# Connect.net
KiCad netlist of a schematic drawn in Altium Designer
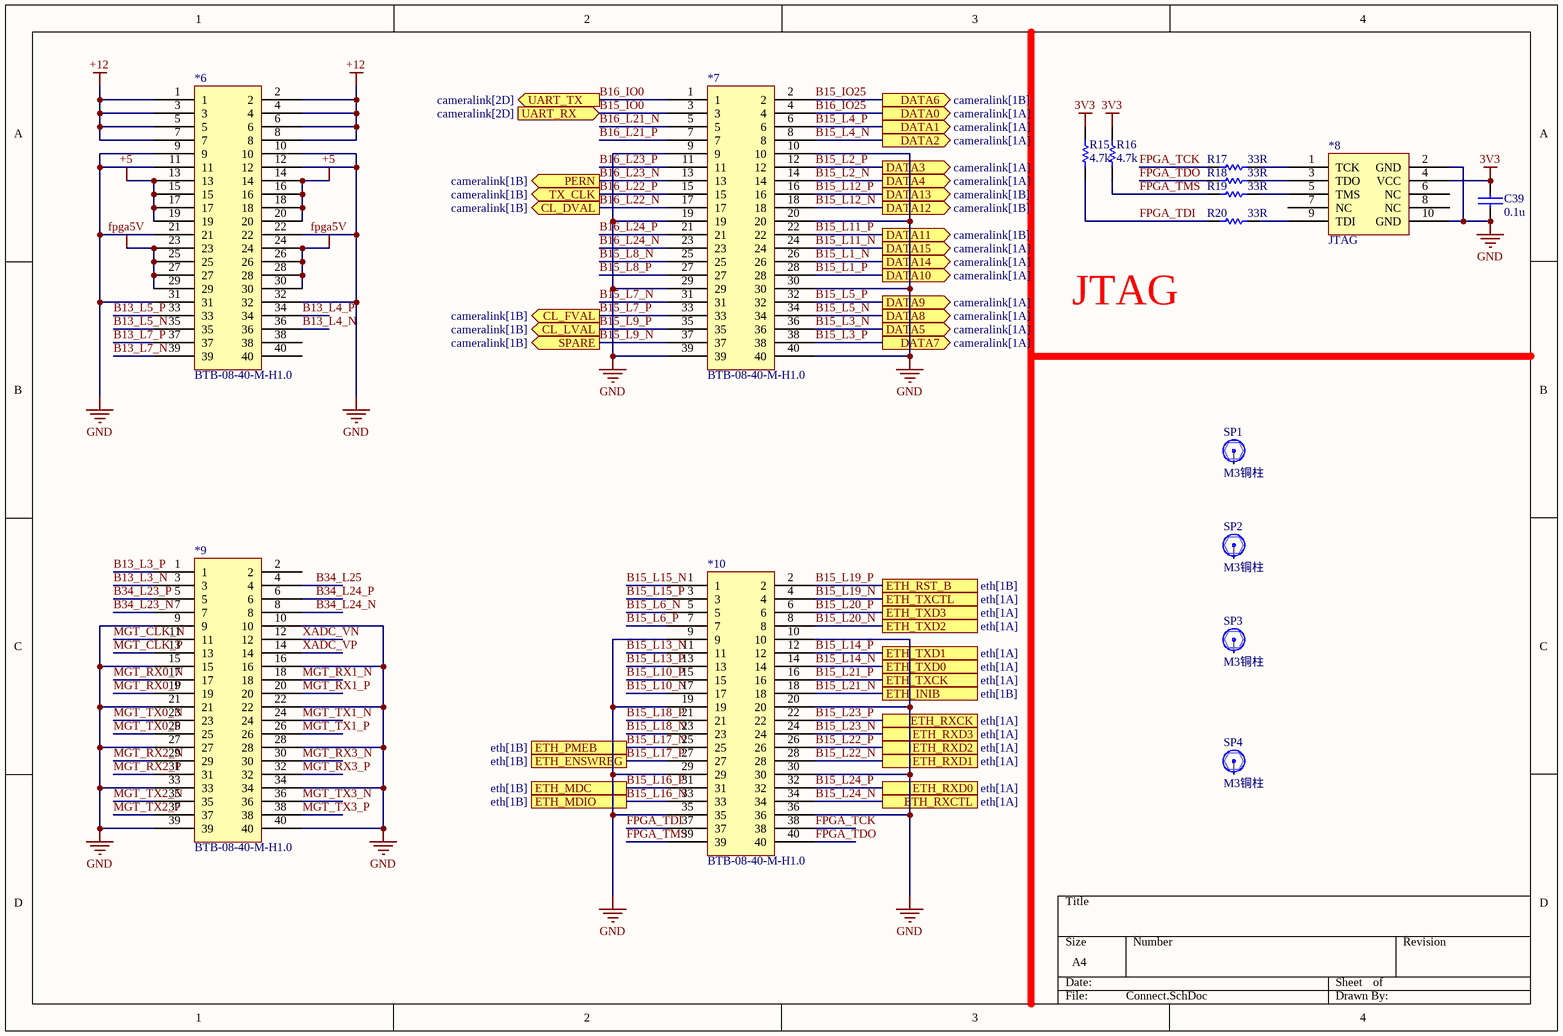
[diagram p0: Connect.SchDoc]

(export (version "E")
  (design (tool "Eeschema 10.0.6"))
  (components
    (comp (ref "*6")
      (value "BTB-08-40-M-H1.0")
      (footprint "BTB-08-40-M-H1.0")
      (libsource (lib "0.04连接器") (part "BTB-08-40-M-H1.0"))
    )
    (comp (ref "*7")
      (value "BTB-08-40-M-H1.0")
      (footprint "BTB-08-40-M-H1.0")
      (libsource (lib "0.04连接器") (part "BTB-08-40-M-H1.0"))
    )
    (comp (ref "*8")
      (value "JTAG")
      (footprint "IDC-TH_10P-P2.54-H-R2-C5-S2.54")
      (libsource (lib "0.05-mylib") (part "JTAG"))
    )
    (comp (ref "*9")
      (value "BTB-08-40-M-H1.0")
      (footprint "BTB-08-40-M-H1.0")
      (libsource (lib "0.04连接器") (part "BTB-08-40-M-H1.0"))
    )
    (comp (ref "*10")
      (value "BTB-08-40-M-H1.0")
      (footprint "BTB-08-40-M-H1.0")
      (libsource (lib "0.04连接器") (part "BTB-08-40-M-H1.0"))
    )
    (comp (ref "C39")
      (value "0.1u")
      (footprint "0603C")
      (description "无极性电容")
      (libsource (lib "1.00-阻容感") (part "CAP"))
    )
    (comp (ref "R15")
      (value "4.7k")
      (footprint "0603R")
      (description "电阻")
      (libsource (lib "1.00-阻容感") (part "RES"))
    )
    (comp (ref "R16")
      (value "4.7k")
      (footprint "0603R")
      (description "电阻")
      (libsource (lib "1.00-阻容感") (part "RES"))
    )
    (comp (ref "R17")
      (value "33R")
      (footprint "0603R")
      (description "电阻")
      (libsource (lib "1.00-阻容感") (part "RES"))
    )
    (comp (ref "R18")
      (value "33R")
      (footprint "0603R")
      (description "电阻")
      (libsource (lib "1.00-阻容感") (part "RES"))
    )
    (comp (ref "R19")
      (value "33R")
      (footprint "0603R")
      (description "电阻")
      (libsource (lib "1.00-阻容感") (part "RES"))
    )
    (comp (ref "R20")
      (value "33R")
      (footprint "0603R")
      (description "电阻")
      (libsource (lib "1.00-阻容感") (part "RES"))
    )
    (comp (ref "SP1")
      (value "M3铜柱")
      (footprint "M3x4_N")
      (description "铜柱")
      (fields (field (name "版权归属") "封装库来自淘宝 ID：黄晶宝石"))
      (libsource (lib "9.09-固定柱") (part "铜柱大焊盘"))
    )
    (comp (ref "SP2")
      (value "M3铜柱")
      (footprint "M3x4_N")
      (description "铜柱")
      (fields (field (name "版权归属") "封装库来自淘宝 ID：黄晶宝石"))
      (libsource (lib "9.09-固定柱") (part "铜柱大焊盘"))
    )
    (comp (ref "SP3")
      (value "M3铜柱")
      (footprint "M3x4_N")
      (description "铜柱")
      (fields (field (name "版权归属") "封装库来自淘宝 ID：黄晶宝石"))
      (libsource (lib "9.09-固定柱") (part "铜柱大焊盘"))
    )
    (comp (ref "SP4")
      (value "M3铜柱")
      (footprint "M3x4_N")
      (description "铜柱")
      (fields (field (name "版权归属") "封装库来自淘宝 ID：黄晶宝石"))
      (libsource (lib "9.09-固定柱") (part "铜柱大焊盘"))
    )
  )
  (nets
    (net (code "1") (name "+5") (class "Default")
      (node (ref "*6") (pin "13") (pinfunction "13_13") (pintype "passive"))
      (node (ref "*6") (pin "14") (pinfunction "14_14") (pintype "passive"))
      (node (ref "*6") (pin "15") (pinfunction "15_15") (pintype "passive"))
      (node (ref "*6") (pin "16") (pinfunction "16_16") (pintype "passive"))
      (node (ref "*6") (pin "17") (pinfunction "17_17") (pintype "passive"))
      (node (ref "*6") (pin "18") (pinfunction "18_18") (pintype "passive"))
      (node (ref "*6") (pin "19") (pinfunction "19_19") (pintype "passive"))
      (node (ref "*6") (pin "20") (pinfunction "20_20") (pintype "passive"))
    )
    (net (code "2") (name "+12") (class "Default")
      (node (ref "*6") (pin "1") (pinfunction "1_1") (pintype "passive"))
      (node (ref "*6") (pin "2") (pinfunction "2_2") (pintype "passive"))
      (node (ref "*6") (pin "3") (pinfunction "3_3") (pintype "passive"))
      (node (ref "*6") (pin "4") (pinfunction "4_4") (pintype "passive"))
      (node (ref "*6") (pin "5") (pinfunction "5_5") (pintype "passive"))
      (node (ref "*6") (pin "6") (pinfunction "6_6") (pintype "passive"))
      (node (ref "*6") (pin "7") (pinfunction "7_7") (pintype "passive"))
      (node (ref "*6") (pin "8") (pinfunction "8_8") (pintype "passive"))
    )
    (net (code "3") (name "/B13_L3_N") (class "Default")
      (node (ref "*9") (pin "3") (pinfunction "3_3") (pintype "passive"))
    )
    (net (code "4") (name "/B13_L3_P") (class "Default")
      (node (ref "*9") (pin "1") (pinfunction "1_1") (pintype "passive"))
    )
    (net (code "5") (name "/B13_L4_N") (class "Default")
      (node (ref "*6") (pin "36") (pinfunction "36_36") (pintype "passive"))
    )
    (net (code "6") (name "/B13_L4_P") (class "Default")
      (node (ref "*6") (pin "34") (pinfunction "34_34") (pintype "passive"))
    )
    (net (code "7") (name "/B13_L5_N") (class "Default")
      (node (ref "*6") (pin "35") (pinfunction "35_35") (pintype "passive"))
    )
    (net (code "8") (name "/B13_L5_P") (class "Default")
      (node (ref "*6") (pin "33") (pinfunction "33_33") (pintype "passive"))
    )
    (net (code "9") (name "/B13_L7_N") (class "Default")
      (node (ref "*6") (pin "39") (pinfunction "39_39") (pintype "passive"))
    )
    (net (code "10") (name "/B13_L7_P") (class "Default")
      (node (ref "*6") (pin "37") (pinfunction "37_37") (pintype "passive"))
    )
    (net (code "11") (name "/B15_IO0") (class "Default")
      (node (ref "*7") (pin "3") (pinfunction "3_3") (pintype "passive"))
    )
    (net (code "12") (name "/B15_IO25") (class "Default")
      (node (ref "*7") (pin "2") (pinfunction "2_2") (pintype "passive"))
    )
    (net (code "13") (name "/B15_L1_N") (class "Default")
      (node (ref "*7") (pin "26") (pinfunction "26_26") (pintype "passive"))
    )
    (net (code "14") (name "/B15_L1_P") (class "Default")
      (node (ref "*7") (pin "28") (pinfunction "28_28") (pintype "passive"))
    )
    (net (code "15") (name "/B15_L2_N") (class "Default")
      (node (ref "*7") (pin "14") (pinfunction "14_14") (pintype "passive"))
    )
    (net (code "16") (name "/B15_L2_P") (class "Default")
      (node (ref "*7") (pin "12") (pinfunction "12_12") (pintype "passive"))
    )
    (net (code "17") (name "/B15_L3_N") (class "Default")
      (node (ref "*7") (pin "36") (pinfunction "36_36") (pintype "passive"))
    )
    (net (code "18") (name "/B15_L3_P") (class "Default")
      (node (ref "*7") (pin "38") (pinfunction "38_38") (pintype "passive"))
    )
    (net (code "19") (name "/B15_L4_N") (class "Default")
      (node (ref "*7") (pin "8") (pinfunction "8_8") (pintype "passive"))
    )
    (net (code "20") (name "/B15_L4_P") (class "Default")
      (node (ref "*7") (pin "6") (pinfunction "6_6") (pintype "passive"))
    )
    (net (code "21") (name "/B15_L5_N") (class "Default")
      (node (ref "*7") (pin "34") (pinfunction "34_34") (pintype "passive"))
    )
    (net (code "22") (name "/B15_L5_P") (class "Default")
      (node (ref "*7") (pin "32") (pinfunction "32_32") (pintype "passive"))
    )
    (net (code "23") (name "/B15_L6_N") (class "Default")
      (node (ref "*10") (pin "5") (pinfunction "5_5") (pintype "passive"))
    )
    (net (code "24") (name "/B15_L6_P") (class "Default")
      (node (ref "*10") (pin "7") (pinfunction "7_7") (pintype "passive"))
    )
    (net (code "25") (name "/B15_L7_N") (class "Default")
      (node (ref "*7") (pin "31") (pinfunction "31_31") (pintype "passive"))
    )
    (net (code "26") (name "/B15_L7_P") (class "Default")
      (node (ref "*7") (pin "33") (pinfunction "33_33") (pintype "passive"))
    )
    (net (code "27") (name "/B15_L8_N") (class "Default")
      (node (ref "*7") (pin "25") (pinfunction "25_25") (pintype "passive"))
    )
    (net (code "28") (name "/B15_L8_P") (class "Default")
      (node (ref "*7") (pin "27") (pinfunction "27_27") (pintype "passive"))
    )
    (net (code "29") (name "/B15_L9_N") (class "Default")
      (node (ref "*7") (pin "37") (pinfunction "37_37") (pintype "passive"))
    )
    (net (code "30") (name "/B15_L9_P") (class "Default")
      (node (ref "*7") (pin "35") (pinfunction "35_35") (pintype "passive"))
    )
    (net (code "31") (name "/B15_L10_N") (class "Default")
      (node (ref "*10") (pin "17") (pinfunction "17_17") (pintype "passive"))
    )
    (net (code "32") (name "/B15_L10_P") (class "Default")
      (node (ref "*10") (pin "15") (pinfunction "15_15") (pintype "passive"))
    )
    (net (code "33") (name "/B15_L11_N") (class "Default")
      (node (ref "*7") (pin "24") (pinfunction "24_24") (pintype "passive"))
    )
    (net (code "34") (name "/B15_L11_P") (class "Default")
      (node (ref "*7") (pin "22") (pinfunction "22_22") (pintype "passive"))
    )
    (net (code "35") (name "/B15_L12_N") (class "Default")
      (node (ref "*7") (pin "18") (pinfunction "18_18") (pintype "passive"))
    )
    (net (code "36") (name "/B15_L12_P") (class "Default")
      (node (ref "*7") (pin "16") (pinfunction "16_16") (pintype "passive"))
    )
    (net (code "37") (name "/B15_L13_N") (class "Default")
      (node (ref "*10") (pin "11") (pinfunction "11_11") (pintype "passive"))
    )
    (net (code "38") (name "/B15_L13_P") (class "Default")
      (node (ref "*10") (pin "13") (pinfunction "13_13") (pintype "passive"))
    )
    (net (code "39") (name "/B15_L14_N") (class "Default")
      (node (ref "*10") (pin "14") (pinfunction "14_14") (pintype "passive"))
    )
    (net (code "40") (name "/B15_L14_P") (class "Default")
      (node (ref "*10") (pin "12") (pinfunction "12_12") (pintype "passive"))
    )
    (net (code "41") (name "/B15_L15_N") (class "Default")
      (node (ref "*10") (pin "1") (pinfunction "1_1") (pintype "passive"))
    )
    (net (code "42") (name "/B15_L15_P") (class "Default")
      (node (ref "*10") (pin "3") (pinfunction "3_3") (pintype "passive"))
    )
    (net (code "43") (name "/B15_L16_N") (class "Default")
      (node (ref "*10") (pin "33") (pinfunction "33_33") (pintype "passive"))
    )
    (net (code "44") (name "/B15_L16_P") (class "Default")
      (node (ref "*10") (pin "31") (pinfunction "31_31") (pintype "passive"))
    )
    (net (code "45") (name "/B15_L17_N") (class "Default")
      (node (ref "*10") (pin "25") (pinfunction "25_25") (pintype "passive"))
    )
    (net (code "46") (name "/B15_L17_P") (class "Default")
      (node (ref "*10") (pin "27") (pinfunction "27_27") (pintype "passive"))
    )
    (net (code "47") (name "/B15_L18_N") (class "Default")
      (node (ref "*10") (pin "23") (pinfunction "23_23") (pintype "passive"))
    )
    (net (code "48") (name "/B15_L18_P") (class "Default")
      (node (ref "*10") (pin "21") (pinfunction "21_21") (pintype "passive"))
    )
    (net (code "49") (name "/B15_L19_N") (class "Default")
      (node (ref "*10") (pin "4") (pinfunction "4_4") (pintype "passive"))
    )
    (net (code "50") (name "/B15_L19_P") (class "Default")
      (node (ref "*10") (pin "2") (pinfunction "2_2") (pintype "passive"))
    )
    (net (code "51") (name "/B15_L20_N") (class "Default")
      (node (ref "*10") (pin "8") (pinfunction "8_8") (pintype "passive"))
    )
    (net (code "52") (name "/B15_L20_P") (class "Default")
      (node (ref "*10") (pin "6") (pinfunction "6_6") (pintype "passive"))
    )
    (net (code "53") (name "/B15_L21_N") (class "Default")
      (node (ref "*10") (pin "18") (pinfunction "18_18") (pintype "passive"))
    )
    (net (code "54") (name "/B15_L21_P") (class "Default")
      (node (ref "*10") (pin "16") (pinfunction "16_16") (pintype "passive"))
    )
    (net (code "55") (name "/B15_L22_N") (class "Default")
      (node (ref "*10") (pin "28") (pinfunction "28_28") (pintype "passive"))
    )
    (net (code "56") (name "/B15_L22_P") (class "Default")
      (node (ref "*10") (pin "26") (pinfunction "26_26") (pintype "passive"))
    )
    (net (code "57") (name "/B15_L23_N") (class "Default")
      (node (ref "*10") (pin "24") (pinfunction "24_24") (pintype "passive"))
    )
    (net (code "58") (name "/B15_L23_P") (class "Default")
      (node (ref "*10") (pin "22") (pinfunction "22_22") (pintype "passive"))
    )
    (net (code "59") (name "/B15_L24_N") (class "Default")
      (node (ref "*10") (pin "34") (pinfunction "34_34") (pintype "passive"))
    )
    (net (code "60") (name "/B15_L24_P") (class "Default")
      (node (ref "*10") (pin "32") (pinfunction "32_32") (pintype "passive"))
    )
    (net (code "61") (name "/B16_IO0") (class "Default")
      (node (ref "*7") (pin "1") (pinfunction "1_1") (pintype "passive"))
    )
    (net (code "62") (name "/B16_IO25") (class "Default")
      (node (ref "*7") (pin "4") (pinfunction "4_4") (pintype "passive"))
    )
    (net (code "63") (name "/B16_L21_N") (class "Default")
      (node (ref "*7") (pin "5") (pinfunction "5_5") (pintype "passive"))
    )
    (net (code "64") (name "/B16_L21_P") (class "Default")
      (node (ref "*7") (pin "7") (pinfunction "7_7") (pintype "passive"))
    )
    (net (code "65") (name "/B16_L22_N") (class "Default")
      (node (ref "*7") (pin "17") (pinfunction "17_17") (pintype "passive"))
    )
    (net (code "66") (name "/B16_L22_P") (class "Default")
      (node (ref "*7") (pin "15") (pinfunction "15_15") (pintype "passive"))
    )
    (net (code "67") (name "/B16_L23_N") (class "Default")
      (node (ref "*7") (pin "13") (pinfunction "13_13") (pintype "passive"))
    )
    (net (code "68") (name "/B16_L23_P") (class "Default")
      (node (ref "*7") (pin "11") (pinfunction "11_11") (pintype "passive"))
    )
    (net (code "69") (name "/B16_L24_N") (class "Default")
      (node (ref "*7") (pin "23") (pinfunction "23_23") (pintype "passive"))
    )
    (net (code "70") (name "/B16_L24_P") (class "Default")
      (node (ref "*7") (pin "21") (pinfunction "21_21") (pintype "passive"))
    )
    (net (code "71") (name "/B34_L23_N") (class "Default")
      (node (ref "*9") (pin "7") (pinfunction "7_7") (pintype "passive"))
    )
    (net (code "72") (name "/B34_L23_P") (class "Default")
      (node (ref "*9") (pin "5") (pinfunction "5_5") (pintype "passive"))
    )
    (net (code "73") (name "/B34_L24_N") (class "Default")
      (node (ref "*9") (pin "8") (pinfunction "8_8") (pintype "passive"))
    )
    (net (code "74") (name "/B34_L24_P") (class "Default")
      (node (ref "*9") (pin "6") (pinfunction "6_6") (pintype "passive"))
    )
    (net (code "75") (name "/B34_L25") (class "Default")
      (node (ref "*9") (pin "4") (pinfunction "4_4") (pintype "passive"))
    )
    (net (code "76") (name "/FPGA_TCK") (class "Default")
      (node (ref "*10") (pin "38") (pinfunction "38_38") (pintype "passive"))
      (node (ref "R17") (pin "1") (pinfunction "1_1") (pintype "passive"))
    )
    (net (code "77") (name "/FPGA_TDI") (class "Default")
      (node (ref "*10") (pin "37") (pinfunction "37_37") (pintype "passive"))
      (node (ref "R15") (pin "1") (pinfunction "1_1") (pintype "passive"))
      (node (ref "R20") (pin "1") (pinfunction "1_1") (pintype "passive"))
    )
    (net (code "78") (name "/FPGA_TDO") (class "Default")
      (node (ref "*10") (pin "40") (pinfunction "40_40") (pintype "passive"))
      (node (ref "R18") (pin "1") (pinfunction "1_1") (pintype "passive"))
    )
    (net (code "79") (name "/FPGA_TMS") (class "Default")
      (node (ref "*10") (pin "39") (pinfunction "39_39") (pintype "passive"))
      (node (ref "R16") (pin "1") (pinfunction "1_1") (pintype "passive"))
      (node (ref "R19") (pin "1") (pinfunction "1_1") (pintype "passive"))
    )
    (net (code "80") (name "/MGT_CLK_N") (class "Default")
      (node (ref "*9") (pin "11") (pinfunction "11_11") (pintype "passive"))
    )
    (net (code "81") (name "/MGT_CLK_P") (class "Default")
      (node (ref "*9") (pin "13") (pinfunction "13_13") (pintype "passive"))
    )
    (net (code "82") (name "/MGT_RX0_N") (class "Default")
      (node (ref "*9") (pin "17") (pinfunction "17_17") (pintype "passive"))
    )
    (net (code "83") (name "/MGT_RX0_P") (class "Default")
      (node (ref "*9") (pin "19") (pinfunction "19_19") (pintype "passive"))
    )
    (net (code "84") (name "/MGT_RX1_N") (class "Default")
      (node (ref "*9") (pin "18") (pinfunction "18_18") (pintype "passive"))
    )
    (net (code "85") (name "/MGT_RX1_P") (class "Default")
      (node (ref "*9") (pin "20") (pinfunction "20_20") (pintype "passive"))
    )
    (net (code "86") (name "/MGT_RX2_N") (class "Default")
      (node (ref "*9") (pin "29") (pinfunction "29_29") (pintype "passive"))
    )
    (net (code "87") (name "/MGT_RX2_P") (class "Default")
      (node (ref "*9") (pin "31") (pinfunction "31_31") (pintype "passive"))
    )
    (net (code "88") (name "/MGT_RX3_N") (class "Default")
      (node (ref "*9") (pin "30") (pinfunction "30_30") (pintype "passive"))
    )
    (net (code "89") (name "/MGT_RX3_P") (class "Default")
      (node (ref "*9") (pin "32") (pinfunction "32_32") (pintype "passive"))
    )
    (net (code "90") (name "/MGT_TX0_N") (class "Default")
      (node (ref "*9") (pin "23") (pinfunction "23_23") (pintype "passive"))
    )
    (net (code "91") (name "/MGT_TX0_P") (class "Default")
      (node (ref "*9") (pin "25") (pinfunction "25_25") (pintype "passive"))
    )
    (net (code "92") (name "/MGT_TX1_N") (class "Default")
      (node (ref "*9") (pin "24") (pinfunction "24_24") (pintype "passive"))
    )
    (net (code "93") (name "/MGT_TX1_P") (class "Default")
      (node (ref "*9") (pin "26") (pinfunction "26_26") (pintype "passive"))
    )
    (net (code "94") (name "/MGT_TX2_N") (class "Default")
      (node (ref "*9") (pin "35") (pinfunction "35_35") (pintype "passive"))
    )
    (net (code "95") (name "/MGT_TX2_P") (class "Default")
      (node (ref "*9") (pin "37") (pinfunction "37_37") (pintype "passive"))
    )
    (net (code "96") (name "/MGT_TX3_N") (class "Default")
      (node (ref "*9") (pin "36") (pinfunction "36_36") (pintype "passive"))
    )
    (net (code "97") (name "/MGT_TX3_P") (class "Default")
      (node (ref "*9") (pin "38") (pinfunction "38_38") (pintype "passive"))
    )
    (net (code "98") (name "/XADC_VN") (class "Default")
      (node (ref "*9") (pin "12") (pinfunction "12_12") (pintype "passive"))
    )
    (net (code "99") (name "/XADC_VP") (class "Default")
      (node (ref "*9") (pin "14") (pinfunction "14_14") (pintype "passive"))
    )
    (net (code "100") (name "3V3") (class "Default")
      (node (ref "*8") (pin "4") (pinfunction "VCC_4") (pintype "passive"))
      (node (ref "C39") (pin "2") (pinfunction "2_2") (pintype "passive"))
      (node (ref "R15") (pin "2") (pinfunction "2_2") (pintype "passive"))
      (node (ref "R16") (pin "2") (pinfunction "2_2") (pintype "passive"))
    )
    (net (code "101") (name "GND") (class "Default")
      (node (ref "*10") (pin "10") (pinfunction "10_10") (pintype "passive"))
      (node (ref "*10") (pin "19") (pinfunction "19_19") (pintype "passive"))
      (node (ref "*10") (pin "20") (pinfunction "20_20") (pintype "passive"))
      (node (ref "*10") (pin "29") (pinfunction "29_29") (pintype "passive"))
      (node (ref "*10") (pin "30") (pinfunction "30_30") (pintype "passive"))
      (node (ref "*10") (pin "35") (pinfunction "35_35") (pintype "passive"))
      (node (ref "*10") (pin "36") (pinfunction "36_36") (pintype "passive"))
      (node (ref "*10") (pin "9") (pinfunction "9_9") (pintype "passive"))
      (node (ref "*6") (pin "10") (pinfunction "10_10") (pintype "passive"))
      (node (ref "*6") (pin "11") (pinfunction "11_11") (pintype "passive"))
      (node (ref "*6") (pin "12") (pinfunction "12_12") (pintype "passive"))
      (node (ref "*6") (pin "21") (pinfunction "21_21") (pintype "passive"))
      (node (ref "*6") (pin "22") (pinfunction "22_22") (pintype "passive"))
      (node (ref "*6") (pin "31") (pinfunction "31_31") (pintype "passive"))
      (node (ref "*6") (pin "32") (pinfunction "32_32") (pintype "passive"))
      (node (ref "*6") (pin "9") (pinfunction "9_9") (pintype "passive"))
      (node (ref "*7") (pin "10") (pinfunction "10_10") (pintype "passive"))
      (node (ref "*7") (pin "19") (pinfunction "19_19") (pintype "passive"))
      (node (ref "*7") (pin "20") (pinfunction "20_20") (pintype "passive"))
      (node (ref "*7") (pin "29") (pinfunction "29_29") (pintype "passive"))
      (node (ref "*7") (pin "30") (pinfunction "30_30") (pintype "passive"))
      (node (ref "*7") (pin "39") (pinfunction "39_39") (pintype "passive"))
      (node (ref "*7") (pin "40") (pinfunction "40_40") (pintype "passive"))
      (node (ref "*7") (pin "9") (pinfunction "9_9") (pintype "passive"))
      (node (ref "*8") (pin "10") (pinfunction "GND_10") (pintype "passive"))
      (node (ref "*8") (pin "2") (pinfunction "GND_2") (pintype "passive"))
      (node (ref "*9") (pin "10") (pinfunction "10_10") (pintype "passive"))
      (node (ref "*9") (pin "15") (pinfunction "15_15") (pintype "passive"))
      (node (ref "*9") (pin "16") (pinfunction "16_16") (pintype "passive"))
      (node (ref "*9") (pin "21") (pinfunction "21_21") (pintype "passive"))
      (node (ref "*9") (pin "22") (pinfunction "22_22") (pintype "passive"))
      (node (ref "*9") (pin "27") (pinfunction "27_27") (pintype "passive"))
      (node (ref "*9") (pin "28") (pinfunction "28_28") (pintype "passive"))
      (node (ref "*9") (pin "33") (pinfunction "33_33") (pintype "passive"))
      (node (ref "*9") (pin "34") (pinfunction "34_34") (pintype "passive"))
      (node (ref "*9") (pin "39") (pinfunction "39_39") (pintype "passive"))
      (node (ref "*9") (pin "40") (pinfunction "40_40") (pintype "passive"))
      (node (ref "*9") (pin "9") (pinfunction "9_9") (pintype "passive"))
      (node (ref "C39") (pin "1") (pinfunction "1_1") (pintype "passive"))
    )
    (net (code "102") (name "Net-(*8-TCK)") (class "Default")
      (node (ref "*8") (pin "1") (pinfunction "TCK_1") (pintype "passive"))
      (node (ref "R17") (pin "2") (pinfunction "2_2") (pintype "passive"))
    )
    (net (code "103") (name "Net-(*8-TDI)") (class "Default")
      (node (ref "*8") (pin "9") (pinfunction "TDI_9") (pintype "passive"))
      (node (ref "R20") (pin "2") (pinfunction "2_2") (pintype "passive"))
    )
    (net (code "104") (name "Net-(*8-TDO)") (class "Default")
      (node (ref "*8") (pin "3") (pinfunction "TDO_3") (pintype "passive"))
      (node (ref "R18") (pin "2") (pinfunction "2_2") (pintype "passive"))
    )
    (net (code "105") (name "Net-(*8-TMS)") (class "Default")
      (node (ref "*8") (pin "5") (pinfunction "TMS_5") (pintype "passive"))
      (node (ref "R19") (pin "2") (pinfunction "2_2") (pintype "passive"))
    )
    (net (code "106") (name "fpga5V") (class "Default")
      (node (ref "*6") (pin "23") (pinfunction "23_23") (pintype "passive"))
      (node (ref "*6") (pin "24") (pinfunction "24_24") (pintype "passive"))
      (node (ref "*6") (pin "25") (pinfunction "25_25") (pintype "passive"))
      (node (ref "*6") (pin "26") (pinfunction "26_26") (pintype "passive"))
      (node (ref "*6") (pin "27") (pinfunction "27_27") (pintype "passive"))
      (node (ref "*6") (pin "28") (pinfunction "28_28") (pintype "passive"))
      (node (ref "*6") (pin "29") (pinfunction "29_29") (pintype "passive"))
      (node (ref "*6") (pin "30") (pinfunction "30_30") (pintype "passive"))
    )
    (net (code "107") (name "unconnected-(*6-Pad38)") (class "Default")
      (node (ref "*6") (pin "38") (pinfunction "38_38") (pintype "passive"))
    )
    (net (code "108") (name "unconnected-(*6-Pad40)") (class "Default")
      (node (ref "*6") (pin "40") (pinfunction "40_40") (pintype "passive"))
    )
    (net (code "109") (name "unconnected-(*8-NC-Pad6)") (class "Default")
      (node (ref "*8") (pin "6") (pinfunction "NC_6") (pintype "passive"))
    )
    (net (code "110") (name "unconnected-(*8-NC-Pad7)") (class "Default")
      (node (ref "*8") (pin "7") (pinfunction "NC_7") (pintype "passive"))
    )
    (net (code "111") (name "unconnected-(*8-NC-Pad8)") (class "Default")
      (node (ref "*8") (pin "8") (pinfunction "NC_8") (pintype "passive"))
    )
    (net (code "112") (name "unconnected-(*9-Pad2)") (class "Default")
      (node (ref "*9") (pin "2") (pinfunction "2_2") (pintype "passive"))
    )
    (net (code "113") (name "unconnected-(SP1-Pad1)") (class "Default")
      (node (ref "SP1") (pin "1") (pinfunction "1_1") (pintype "passive"))
    )
    (net (code "114") (name "unconnected-(SP2-Pad1)") (class "Default")
      (node (ref "SP2") (pin "1") (pinfunction "1_1") (pintype "passive"))
    )
    (net (code "115") (name "unconnected-(SP3-Pad1)") (class "Default")
      (node (ref "SP3") (pin "1") (pinfunction "1_1") (pintype "passive"))
    )
    (net (code "116") (name "unconnected-(SP4-Pad1)") (class "Default")
      (node (ref "SP4") (pin "1") (pinfunction "1_1") (pintype "passive"))
    )
  )
)
